# XL52832.net
KiCad netlist of a schematic drawn in Altium Designer
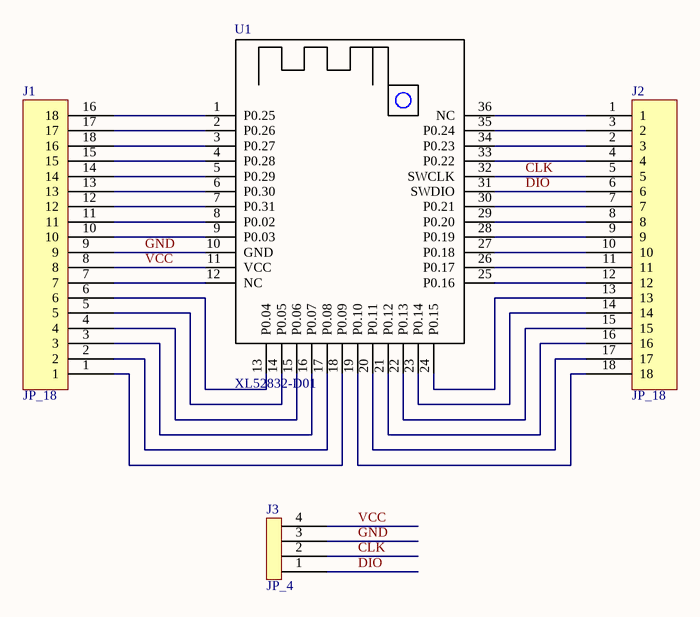
[diagram p0: XL52832.SchDoc]

(export (version "E")
  (design (tool "Eeschema 10.0.6"))
  (components
    (comp (ref "J1") (value "JP_18") (footprint "JP_18") (libsource (lib "") (part "JP_18_1")))
    (comp (ref "J2") (value "JP_18") (footprint "JP_18") (libsource (lib "LuongTanDat") (part "JP_18")))
    (comp (ref "J3") (value "JP_4") (footprint "JP_4") (libsource (lib "LuongTanDat") (part "JP_4")))
    (comp (ref "U1")
      (value "XL52832-D01")
      (footprint "XL52832-D01")
      (libsource (lib "LuongTanDat") (part "XL52832-D01"))
    )
  )
  (nets
    (net (code "1") (name "/CLK") (class "Default")
      (node (ref "J2") (pin "5") (pinfunction "5_5") (pintype "passive"))
      (node (ref "J3") (pin "2") (pinfunction "2_2") (pintype "passive"))
      (node (ref "U1") (pin "32") (pinfunction "SWCLK_32") (pintype "passive"))
    )
    (net (code "2") (name "/DIO") (class "Default")
      (node (ref "J2") (pin "6") (pinfunction "6_6") (pintype "passive"))
      (node (ref "J3") (pin "1") (pinfunction "1_1") (pintype "passive"))
      (node (ref "U1") (pin "31") (pinfunction "SWDIO_31") (pintype "passive"))
    )
    (net (code "3") (name "/GND") (class "Default")
      (node (ref "J1") (pin "9") (pinfunction "9_9") (pintype "passive"))
      (node (ref "J3") (pin "3") (pinfunction "3_3") (pintype "passive"))
      (node (ref "U1") (pin "10") (pinfunction "GND_10") (pintype "passive"))
    )
    (net (code "4") (name "/VCC") (class "Default")
      (node (ref "J1") (pin "8") (pinfunction "8_8") (pintype "passive"))
      (node (ref "J3") (pin "4") (pinfunction "4_4") (pintype "passive"))
      (node (ref "U1") (pin "11") (pinfunction "VCC_11") (pintype "passive"))
    )
    (net (code "5") (name "Net-(J1-16)") (class "Default")
      (node (ref "J1") (pin "18") (pinfunction "16_18") (pintype "passive"))
      (node (ref "U1") (pin "3") (pinfunction "P0.27_3") (pintype "passive"))
    )
    (net (code "6") (name "Net-(J1-18)") (class "Default")
      (node (ref "J1") (pin "16") (pinfunction "18_16") (pintype "passive"))
      (node (ref "U1") (pin "1") (pinfunction "P0.25_1") (pintype "passive"))
    )
    (net (code "7") (name "Net-(J1-Pad7)") (class "Default")
      (node (ref "J1") (pin "7") (pinfunction "7_7") (pintype "passive"))
      (node (ref "U1") (pin "12") (pinfunction "NC_12") (pintype "passive"))
    )
    (net (code "8") (name "Net-(J2-2)") (class "Default")
      (node (ref "J2") (pin "3") (pinfunction "2_3") (pintype "passive"))
      (node (ref "U1") (pin "35") (pinfunction "P0.24_35") (pintype "passive"))
    )
    (net (code "9") (name "Net-(J2-3)") (class "Default")
      (node (ref "J2") (pin "2") (pinfunction "3_2") (pintype "passive"))
      (node (ref "U1") (pin "34") (pinfunction "P0.23_34") (pintype "passive"))
    )
    (net (code "10") (name "Net-(J2-Pad1)") (class "Default")
      (node (ref "J2") (pin "1") (pinfunction "1_1") (pintype "passive"))
      (node (ref "U1") (pin "36") (pinfunction "NC_36") (pintype "passive"))
    )
    (net (code "11") (name "Net-(U1-P0.02)") (class "Default")
      (node (ref "J1") (pin "11") (pinfunction "11_11") (pintype "passive"))
      (node (ref "U1") (pin "8") (pinfunction "P0.02_8") (pintype "passive"))
    )
    (net (code "12") (name "Net-(U1-P0.03)") (class "Default")
      (node (ref "J1") (pin "10") (pinfunction "10_10") (pintype "passive"))
      (node (ref "U1") (pin "9") (pinfunction "P0.03_9") (pintype "passive"))
    )
    (net (code "13") (name "Net-(U1-P0.04)") (class "Default")
      (node (ref "J1") (pin "6") (pinfunction "6_6") (pintype "passive"))
      (node (ref "U1") (pin "13") (pinfunction "P0.04_13") (pintype "passive"))
    )
    (net (code "14") (name "Net-(U1-P0.05)") (class "Default")
      (node (ref "J1") (pin "5") (pinfunction "5_5") (pintype "passive"))
      (node (ref "U1") (pin "14") (pinfunction "P0.05_14") (pintype "passive"))
    )
    (net (code "15") (name "Net-(U1-P0.06)") (class "Default")
      (node (ref "J1") (pin "4") (pinfunction "4_4") (pintype "passive"))
      (node (ref "U1") (pin "15") (pinfunction "P0.06_15") (pintype "passive"))
    )
    (net (code "16") (name "Net-(U1-P0.07)") (class "Default")
      (node (ref "J1") (pin "3") (pinfunction "3_3") (pintype "passive"))
      (node (ref "U1") (pin "16") (pinfunction "P0.07_16") (pintype "passive"))
    )
    (net (code "17") (name "Net-(U1-P0.08)") (class "Default")
      (node (ref "J1") (pin "2") (pinfunction "2_2") (pintype "passive"))
      (node (ref "U1") (pin "17") (pinfunction "P0.08_17") (pintype "passive"))
    )
    (net (code "18") (name "Net-(U1-P0.09)") (class "Default")
      (node (ref "J1") (pin "1") (pinfunction "1_1") (pintype "passive"))
      (node (ref "U1") (pin "18") (pinfunction "P0.09_18") (pintype "passive"))
    )
    (net (code "19") (name "Net-(U1-P0.10)") (class "Default")
      (node (ref "J2") (pin "18") (pinfunction "18_18") (pintype "passive"))
      (node (ref "U1") (pin "19") (pinfunction "P0.10_19") (pintype "passive"))
    )
    (net (code "20") (name "Net-(U1-P0.11)") (class "Default")
      (node (ref "J2") (pin "17") (pinfunction "17_17") (pintype "passive"))
      (node (ref "U1") (pin "20") (pinfunction "P0.11_20") (pintype "passive"))
    )
    (net (code "21") (name "Net-(U1-P0.12)") (class "Default")
      (node (ref "J2") (pin "16") (pinfunction "16_16") (pintype "passive"))
      (node (ref "U1") (pin "21") (pinfunction "P0.12_21") (pintype "passive"))
    )
    (net (code "22") (name "Net-(U1-P0.13)") (class "Default")
      (node (ref "J2") (pin "15") (pinfunction "15_15") (pintype "passive"))
      (node (ref "U1") (pin "22") (pinfunction "P0.13_22") (pintype "passive"))
    )
    (net (code "23") (name "Net-(U1-P0.14)") (class "Default")
      (node (ref "J2") (pin "14") (pinfunction "14_14") (pintype "passive"))
      (node (ref "U1") (pin "23") (pinfunction "P0.14_23") (pintype "passive"))
    )
    (net (code "24") (name "Net-(U1-P0.15)") (class "Default")
      (node (ref "J2") (pin "13") (pinfunction "13_13") (pintype "passive"))
      (node (ref "U1") (pin "24") (pinfunction "P0.15_24") (pintype "passive"))
    )
    (net (code "25") (name "Net-(U1-P0.16)") (class "Default")
      (node (ref "J2") (pin "12") (pinfunction "12_12") (pintype "passive"))
      (node (ref "U1") (pin "25") (pinfunction "P0.16_25") (pintype "passive"))
    )
    (net (code "26") (name "Net-(U1-P0.17)") (class "Default")
      (node (ref "J2") (pin "11") (pinfunction "11_11") (pintype "passive"))
      (node (ref "U1") (pin "26") (pinfunction "P0.17_26") (pintype "passive"))
    )
    (net (code "27") (name "Net-(U1-P0.18)") (class "Default")
      (node (ref "J2") (pin "10") (pinfunction "10_10") (pintype "passive"))
      (node (ref "U1") (pin "27") (pinfunction "P0.18_27") (pintype "passive"))
    )
    (net (code "28") (name "Net-(U1-P0.19)") (class "Default")
      (node (ref "J2") (pin "9") (pinfunction "9_9") (pintype "passive"))
      (node (ref "U1") (pin "28") (pinfunction "P0.19_28") (pintype "passive"))
    )
    (net (code "29") (name "Net-(U1-P0.20)") (class "Default")
      (node (ref "J2") (pin "8") (pinfunction "8_8") (pintype "passive"))
      (node (ref "U1") (pin "29") (pinfunction "P0.20_29") (pintype "passive"))
    )
    (net (code "30") (name "Net-(U1-P0.21)") (class "Default")
      (node (ref "J2") (pin "7") (pinfunction "7_7") (pintype "passive"))
      (node (ref "U1") (pin "30") (pinfunction "P0.21_30") (pintype "passive"))
    )
    (net (code "31") (name "Net-(U1-P0.22)") (class "Default")
      (node (ref "J2") (pin "4") (pinfunction "4_4") (pintype "passive"))
      (node (ref "U1") (pin "33") (pinfunction "P0.22_33") (pintype "passive"))
    )
    (net (code "32") (name "Net-(U1-P0.26)") (class "Default")
      (node (ref "J1") (pin "17") (pinfunction "17_17") (pintype "passive"))
      (node (ref "U1") (pin "2") (pinfunction "P0.26_2") (pintype "passive"))
    )
    (net (code "33") (name "Net-(U1-P0.28)") (class "Default")
      (node (ref "J1") (pin "15") (pinfunction "15_15") (pintype "passive"))
      (node (ref "U1") (pin "4") (pinfunction "P0.28_4") (pintype "passive"))
    )
    (net (code "34") (name "Net-(U1-P0.29)") (class "Default")
      (node (ref "J1") (pin "14") (pinfunction "14_14") (pintype "passive"))
      (node (ref "U1") (pin "5") (pinfunction "P0.29_5") (pintype "passive"))
    )
    (net (code "35") (name "Net-(U1-P0.30)") (class "Default")
      (node (ref "J1") (pin "13") (pinfunction "13_13") (pintype "passive"))
      (node (ref "U1") (pin "6") (pinfunction "P0.30_6") (pintype "passive"))
    )
    (net (code "36") (name "Net-(U1-P0.31)") (class "Default")
      (node (ref "J1") (pin "12") (pinfunction "12_12") (pintype "passive"))
      (node (ref "U1") (pin "7") (pinfunction "P0.31_7") (pintype "passive"))
    )
  )
)
